# Power.net
KiCad netlist of a schematic drawn in Altium Designer
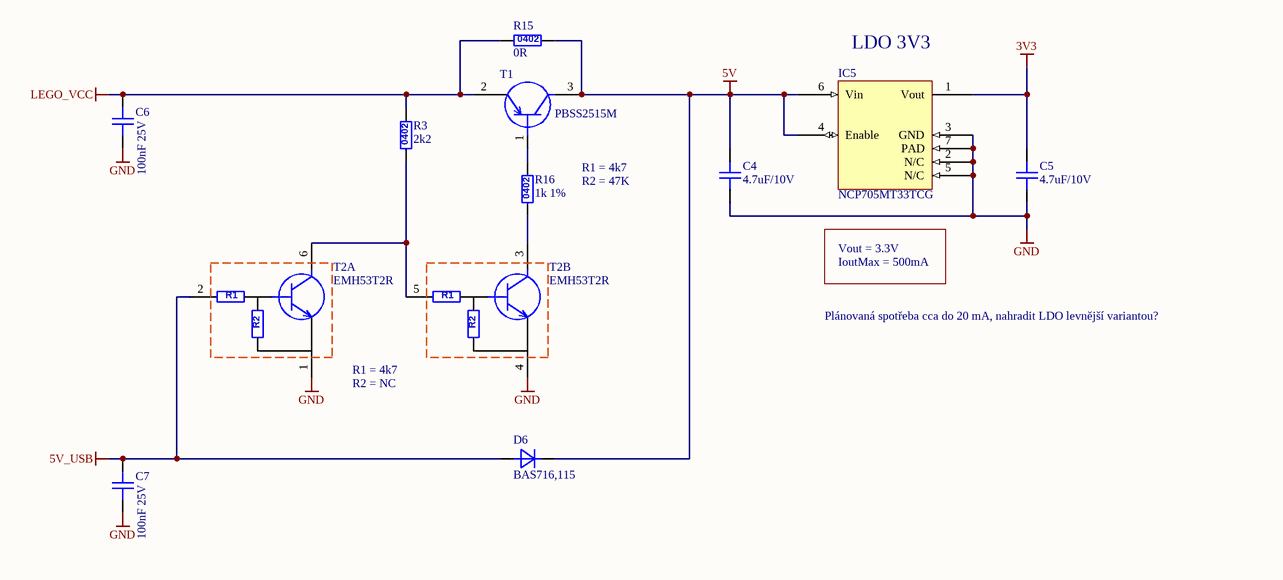
[diagram p0: Power.SchDoc]

(export (version "E")
  (design (tool "Eeschema 10.0.6"))
  (components
    (comp (ref "C4")
      (value "4.7uF/10V")
      (footprint "C0402_big")
      (description "MURATA - GRM155R61A475MEAAD - CAP, MLCC, X5R, 4.7UF, 10V, 0402")
      (fields (field (name "Comment") "UniversalCapacitor"))
      (libsource (lib "UTBStockLib") (part "UniversalCapacitor"))
    )
    (comp (ref "C5")
      (value "4.7uF/10V")
      (footprint "C0402_big")
      (description "MURATA - GRM155R61A475MEAAD - CAP, MLCC, X5R, 4.7UF, 10V, 0402")
      (fields (field (name "Comment") "UniversalCapacitor"))
      (libsource (lib "UTBStockLib") (part "UniversalCapacitor"))
    )
    (comp (ref "C6")
      (value "100nF 25V")
      (footprint "C0402")
      (description "WALSIN - 0402B104K250CT - CAPACITOR, MLCC, X7R, 0.1UF, 25V, 0402")
      (fields (field (name "Comment") "UniversalCapacitor"))
      (libsource (lib "UTBStockLib") (part "UniversalCapacitor"))
    )
    (comp (ref "C7")
      (value "100nF 25V")
      (footprint "C0402")
      (description "WALSIN - 0402B104K250CT - CAPACITOR, MLCC, X7R, 0.1UF, 25V, 0402")
      (fields (field (name "Comment") "UniversalCapacitor"))
      (libsource (lib "UTBStockLib") (part "UniversalCapacitor"))
    )
    (comp (ref "D6")
      (value "BAS716,115")
      (footprint "SOD523")
      (description "NEXPERIA - BAS716,115 - Small Signal Diode, Single, 85 V, 200 mA, 1.25 V, 3 µs, 4 A")
      (fields (field (name "Comment") "Diode"))
      (libsource (lib "UTBStockLib") (part "Diode"))
    )
    (comp (ref "IC5")
      (value "NCP705MT33TCG")
      (footprint "WDFN6")
      (description "Regulátory napětí s nízkým úbytkem (LDO) 500 MA LDO ULTRA-LOW IQ")
      (fields (field (name "Comment") "VoltageRegulator-Fixed08"))
      (libsource (lib "UTBStockLib") (part "VoltageRegulator-Fixed08"))
    )
    (comp (ref "R3")
      (value "2k2")
      (footprint "R0402")
      (description "VISHAY - CRCW04022K20FKED. - RES, THICK FILM, 2K2, 1%, 0.063W, 0402")
      (fields (field (name "Comment") "UniversalResistor0402"))
      (libsource (lib "UTBStockLib") (part "UniversalResistor0402"))
    )
    (comp (ref "R15")
      (value "0R")
      (footprint "R0402")
      (description "VISHAY - CRCW04020000Z0ED - RESISTOR, 0R, 0.063W, JUMPER, 0402, SMD")
      (fields (field (name "Comment") "UniversalResistor0402"))
      (libsource (lib "UTBStockLib") (part "UniversalResistor0402"))
    )
    (comp (ref "R16")
      (value "1k 1%")
      (footprint "R0402")
      (description "VISHAY - CRCW04021K00FKED - RES, THICK FILM, 1K, 1%, 0.063W, 0402")
      (fields (field (name "Comment") "UniversalResistor0402"))
      (libsource (lib "UTBStockLib") (part "UniversalResistor0402"))
    )
    (comp (ref "T1")
      (value "PBSS2515M")
      (footprint "DFN1006-3")
      (description "NEXPERIA - PBSS2515M,315 - TRANSISTOR, BIPOLAR")
      (fields (field (name "Comment") "PNP"))
      (libsource (lib "UTBStockLib") (part "PNP"))
    )
    (comp (ref "T2")
      (value "EMH53T2R")
      (footprint "SOT-563-6")
      (description "ROHM - EMH53T2R - Bipolar Pre-Biased / Digital Transistor, Dual NPN, 50 V, 100 mA, 4.7 kohm")
      (fields (field (name "Comment") "NPN_DUAL"))
      (libsource (lib "") (part "NPN_DUAL_1"))
    )
  )
  (nets
    (net (code "1") (name "3V3") (class "Default")
      (node (ref "C5") (pin "1") (pinfunction "1_1") (pintype "passive"))
      (node (ref "IC5") (pin "1") (pinfunction "Vout_1") (pintype "passive"))
    )
    (net (code "2") (name "5V") (class "Default")
      (node (ref "C4") (pin "1") (pinfunction "1_1") (pintype "passive"))
      (node (ref "D6") (pin "2") (pinfunction "C_2") (pintype "passive"))
      (node (ref "IC5") (pin "4") (pinfunction "Enable_4") (pintype "bidirectional"))
      (node (ref "IC5") (pin "6") (pinfunction "Vin_6") (pintype "input"))
      (node (ref "R15") (pin "1") (pinfunction "1_1") (pintype "passive"))
      (node (ref "T1") (pin "3") (pinfunction "C_3") (pintype "passive"))
    )
    (net (code "3") (name "5V_USB") (class "Default")
      (node (ref "C7") (pin "2") (pinfunction "2_2") (pintype "passive"))
      (node (ref "D6") (pin "1") (pinfunction "A_1") (pintype "passive"))
      (node (ref "T2") (pin "2") (pinfunction "E_2") (pintype "passive"))
    )
    (net (code "4") (name "GND") (class "Default")
      (node (ref "C4") (pin "2") (pinfunction "2_2") (pintype "passive"))
      (node (ref "C5") (pin "2") (pinfunction "2_2") (pintype "passive"))
      (node (ref "C6") (pin "1") (pinfunction "1_1") (pintype "passive"))
      (node (ref "C7") (pin "1") (pinfunction "1_1") (pintype "passive"))
      (node (ref "IC5") (pin "2") (pinfunction "N/C_2") (pintype "input"))
      (node (ref "IC5") (pin "3") (pinfunction "GND_3") (pintype "input"))
      (node (ref "IC5") (pin "5") (pinfunction "N/C_5") (pintype "input"))
      (node (ref "IC5") (pin "7") (pinfunction "PAD_7") (pintype "input"))
      (node (ref "T2") (pin "1") (pinfunction "B_1") (pintype "passive"))
      (node (ref "T2") (pin "4") (pinfunction "e_4") (pintype "passive"))
    )
    (net (code "5") (name "LEGO_VCC") (class "Default")
      (node (ref "C6") (pin "2") (pinfunction "2_2") (pintype "passive"))
      (node (ref "R15") (pin "2") (pinfunction "2_2") (pintype "passive"))
      (node (ref "R3") (pin "1") (pinfunction "1_1") (pintype "passive"))
      (node (ref "T1") (pin "2") (pinfunction "E_2") (pintype "passive"))
    )
    (net (code "6") (name "Net-(T1-B)") (class "Default")
      (node (ref "R16") (pin "1") (pinfunction "1_1") (pintype "passive"))
      (node (ref "T1") (pin "1") (pinfunction "B_1") (pintype "passive"))
    )
    (net (code "7") (name "Net-(T2A-C)") (class "Default")
      (node (ref "R3") (pin "2") (pinfunction "2_2") (pintype "passive"))
      (node (ref "T2") (pin "5") (pinfunction "E_5") (pintype "passive"))
      (node (ref "T2") (pin "6") (pinfunction "C_6") (pintype "passive"))
    )
    (net (code "8") (name "Net-(T2B-C)") (class "Default")
      (node (ref "R16") (pin "2") (pinfunction "2_2") (pintype "passive"))
      (node (ref "T2") (pin "3") (pinfunction "C_3") (pintype "passive"))
    )
  )
)
